# carm2.net
KiCad netlist of a schematic drawn in EAGLE
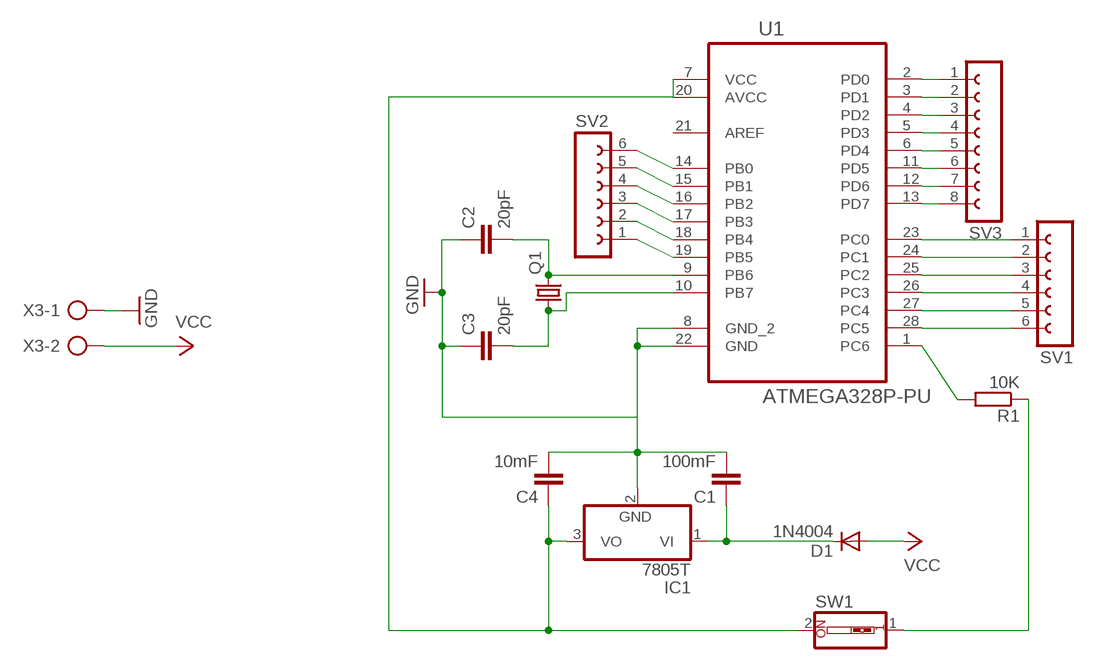
[diagram p0: schematic, sheet 1]

(export (version "E")
  (design (tool "Eeschema 10.0.6"))
  (components
    (comp (ref "C1")
      (value "100mF")
      (footprint "eagle-import:C10B4")
      (libsource (lib "eagle-import") (part "C10/4"))
    )
    (comp (ref "C2")
      (value "20pF")
      (footprint "eagle-import:C10B4")
      (libsource (lib "eagle-import") (part "C10/4"))
    )
    (comp (ref "C3")
      (value "20pF")
      (footprint "eagle-import:C10B4")
      (libsource (lib "eagle-import") (part "C10/4"))
    )
    (comp (ref "C4")
      (value "10mF")
      (footprint "eagle-import:C10B4")
      (libsource (lib "eagle-import") (part "C10/4"))
    )
    (comp (ref "D1")
      (value "1N4004")
      (footprint "eagle-import:DO41-10")
      (libsource (lib "eagle-import") (part "1N4004"))
    )
    (comp (ref "IC1")
      (value "7805T")
      (footprint "eagle-import:TO220H")
      (libsource (lib "eagle-import") (part "78T05"))
    )
    (comp (ref "Q1")
      (value "CRYSTALHC49S")
      (footprint "eagle-import:HC49_S")
      (libsource (lib "eagle-import") (part "CRYSTALHC49S"))
    )
    (comp (ref "R1")
      (value "10K")
      (footprint "eagle-import:0207_10")
      (libsource (lib "eagle-import") (part "R-EU_0207/10"))
    )
    (comp (ref "SV1")
      (value "FE06-1")
      (footprint "eagle-import:FE06")
      (libsource (lib "eagle-import") (part "FE06-1"))
    )
    (comp (ref "SV2")
      (value "FE06-1")
      (footprint "eagle-import:FE06")
      (libsource (lib "eagle-import") (part "FE06-1"))
    )
    (comp (ref "SV3")
      (value "FE08-1")
      (footprint "eagle-import:FE08")
      (libsource (lib "eagle-import") (part "FE08-1"))
    )
    (comp (ref "SW1")
      (value "SW_DIP-1")
      (footprint "eagle-import:EDG-01")
      (libsource (lib "eagle-import") (part "SW_DIP-1"))
    )
    (comp (ref "U1")
      (value "ATMEGA328P-PU")
      (footprint "eagle-import:DIP254P762X457-28")
      (libsource (lib "eagle-import") (part "ATMEGA328P-PU"))
    )
    (comp (ref "X3")
      (value "AK300/2")
      (footprint "eagle-import:AK300_2")
      (libsource (lib "eagle-import") (part "AK300/2"))
    )
  )
  (nets
    (net (code "1") (name "GND") (class "Default")
      (node (ref "C1") (pin "2") (pinfunction "2_2") (pintype "passive"))
      (node (ref "C2") (pin "1") (pinfunction "1_1") (pintype "passive"))
      (node (ref "C3") (pin "1") (pinfunction "1_1") (pintype "passive"))
      (node (ref "C4") (pin "2") (pinfunction "2_2") (pintype "passive"))
      (node (ref "IC1") (pin "2") (pinfunction "GND_2") (pintype "passive"))
      (node (ref "U1") (pin "22") (pinfunction "GND_22") (pintype "passive"))
      (node (ref "U1") (pin "8") (pinfunction "GND_2_8") (pintype "passive"))
      (node (ref "X3") (pin "1") (pinfunction "KL_1") (pintype "passive"))
    )
    (net (code "2") (name "Net-(IC1-VI)") (class "Default")
      (node (ref "C1") (pin "1") (pinfunction "1_1") (pintype "passive"))
      (node (ref "D1") (pin "C") (pinfunction "C_C") (pintype "passive"))
      (node (ref "IC1") (pin "1") (pinfunction "VI_1") (pintype "input"))
    )
    (net (code "3") (name "Net-(IC1-VO)") (class "Default")
      (node (ref "C4") (pin "1") (pinfunction "1_1") (pintype "passive"))
      (node (ref "IC1") (pin "3") (pinfunction "VO_3") (pintype "passive"))
      (node (ref "SW1") (pin "2") (pinfunction "2_2") (pintype "passive"))
      (node (ref "U1") (pin "20") (pinfunction "AVCC_20") (pintype "power_in"))
      (node (ref "U1") (pin "7") (pinfunction "VCC_7") (pintype "power_in"))
    )
    (net (code "4") (name "Net-(R1-Pad1)") (class "Default")
      (node (ref "R1") (pin "1") (pinfunction "1_1") (pintype "passive"))
      (node (ref "SW1") (pin "1") (pinfunction "1_1") (pintype "passive"))
    )
    (net (code "5") (name "Net-(U1-PB0)") (class "Default")
      (node (ref "SV2") (pin "6") (pinfunction "6_6") (pintype "passive"))
      (node (ref "U1") (pin "14") (pinfunction "PB0_14") (pintype "bidirectional"))
    )
    (net (code "6") (name "Net-(U1-PB1)") (class "Default")
      (node (ref "SV2") (pin "5") (pinfunction "5_5") (pintype "passive"))
      (node (ref "U1") (pin "15") (pinfunction "PB1_15") (pintype "bidirectional"))
    )
    (net (code "7") (name "Net-(U1-PB2)") (class "Default")
      (node (ref "SV2") (pin "4") (pinfunction "4_4") (pintype "passive"))
      (node (ref "U1") (pin "16") (pinfunction "PB2_16") (pintype "bidirectional"))
    )
    (net (code "8") (name "Net-(U1-PB3)") (class "Default")
      (node (ref "SV2") (pin "3") (pinfunction "3_3") (pintype "passive"))
      (node (ref "U1") (pin "17") (pinfunction "PB3_17") (pintype "bidirectional"))
    )
    (net (code "9") (name "Net-(U1-PB4)") (class "Default")
      (node (ref "SV2") (pin "2") (pinfunction "2_2") (pintype "passive"))
      (node (ref "U1") (pin "18") (pinfunction "PB4_18") (pintype "bidirectional"))
    )
    (net (code "10") (name "Net-(U1-PB5)") (class "Default")
      (node (ref "SV2") (pin "1") (pinfunction "1_1") (pintype "passive"))
      (node (ref "U1") (pin "19") (pinfunction "PB5_19") (pintype "bidirectional"))
    )
    (net (code "11") (name "Net-(U1-PB6)") (class "Default")
      (node (ref "C2") (pin "2") (pinfunction "2_2") (pintype "passive"))
      (node (ref "Q1") (pin "2") (pinfunction "2_2") (pintype "passive"))
      (node (ref "U1") (pin "9") (pinfunction "PB6_9") (pintype "bidirectional"))
    )
    (net (code "12") (name "Net-(U1-PB7)") (class "Default")
      (node (ref "C3") (pin "2") (pinfunction "2_2") (pintype "passive"))
      (node (ref "Q1") (pin "1") (pinfunction "1_1") (pintype "passive"))
      (node (ref "U1") (pin "10") (pinfunction "PB7_10") (pintype "bidirectional"))
    )
    (net (code "13") (name "Net-(U1-PC0)") (class "Default")
      (node (ref "SV1") (pin "1") (pinfunction "1_1") (pintype "passive"))
      (node (ref "U1") (pin "23") (pinfunction "PC0_23") (pintype "bidirectional"))
    )
    (net (code "14") (name "Net-(U1-PC1)") (class "Default")
      (node (ref "SV1") (pin "2") (pinfunction "2_2") (pintype "passive"))
      (node (ref "U1") (pin "24") (pinfunction "PC1_24") (pintype "bidirectional"))
    )
    (net (code "15") (name "Net-(U1-PC2)") (class "Default")
      (node (ref "SV1") (pin "3") (pinfunction "3_3") (pintype "passive"))
      (node (ref "U1") (pin "25") (pinfunction "PC2_25") (pintype "bidirectional"))
    )
    (net (code "16") (name "Net-(U1-PC3)") (class "Default")
      (node (ref "SV1") (pin "4") (pinfunction "4_4") (pintype "passive"))
      (node (ref "U1") (pin "26") (pinfunction "PC3_26") (pintype "bidirectional"))
    )
    (net (code "17") (name "Net-(U1-PC4)") (class "Default")
      (node (ref "SV1") (pin "5") (pinfunction "5_5") (pintype "passive"))
      (node (ref "U1") (pin "27") (pinfunction "PC4_27") (pintype "bidirectional"))
    )
    (net (code "18") (name "Net-(U1-PC5)") (class "Default")
      (node (ref "SV1") (pin "6") (pinfunction "6_6") (pintype "passive"))
      (node (ref "U1") (pin "28") (pinfunction "PC5_28") (pintype "bidirectional"))
    )
    (net (code "19") (name "Net-(U1-PC6)") (class "Default")
      (node (ref "R1") (pin "2") (pinfunction "2_2") (pintype "passive"))
      (node (ref "U1") (pin "1") (pinfunction "PC6_1") (pintype "bidirectional"))
    )
    (net (code "20") (name "Net-(U1-PD0)") (class "Default")
      (node (ref "SV3") (pin "1") (pinfunction "1_1") (pintype "passive"))
      (node (ref "U1") (pin "2") (pinfunction "PD0_2") (pintype "bidirectional"))
    )
    (net (code "21") (name "Net-(U1-PD1)") (class "Default")
      (node (ref "SV3") (pin "2") (pinfunction "2_2") (pintype "passive"))
      (node (ref "U1") (pin "3") (pinfunction "PD1_3") (pintype "bidirectional"))
    )
    (net (code "22") (name "Net-(U1-PD2)") (class "Default")
      (node (ref "SV3") (pin "3") (pinfunction "3_3") (pintype "passive"))
      (node (ref "U1") (pin "4") (pinfunction "PD2_4") (pintype "bidirectional"))
    )
    (net (code "23") (name "Net-(U1-PD3)") (class "Default")
      (node (ref "SV3") (pin "4") (pinfunction "4_4") (pintype "passive"))
      (node (ref "U1") (pin "5") (pinfunction "PD3_5") (pintype "bidirectional"))
    )
    (net (code "24") (name "Net-(U1-PD4)") (class "Default")
      (node (ref "SV3") (pin "5") (pinfunction "5_5") (pintype "passive"))
      (node (ref "U1") (pin "6") (pinfunction "PD4_6") (pintype "bidirectional"))
    )
    (net (code "25") (name "Net-(U1-PD5)") (class "Default")
      (node (ref "SV3") (pin "6") (pinfunction "6_6") (pintype "passive"))
      (node (ref "U1") (pin "11") (pinfunction "PD5_11") (pintype "bidirectional"))
    )
    (net (code "26") (name "Net-(U1-PD6)") (class "Default")
      (node (ref "SV3") (pin "7") (pinfunction "7_7") (pintype "passive"))
      (node (ref "U1") (pin "12") (pinfunction "PD6_12") (pintype "bidirectional"))
    )
    (net (code "27") (name "Net-(U1-PD7)") (class "Default")
      (node (ref "SV3") (pin "8") (pinfunction "8_8") (pintype "passive"))
      (node (ref "U1") (pin "13") (pinfunction "PD7_13") (pintype "bidirectional"))
    )
    (net (code "28") (name "VCC") (class "Default")
      (node (ref "D1") (pin "A") (pinfunction "A_A") (pintype "passive"))
      (node (ref "X3") (pin "2") (pinfunction "KL_2") (pintype "passive"))
    )
    (net (code "29") (name "unconnected-(U1-AREF-Pad21)") (class "Default")
      (node (ref "U1") (pin "21") (pinfunction "AREF_21") (pintype "input"))
    )
  )
)
